# 11_Fan.net
KiCad netlist of a schematic drawn in Altium Designer
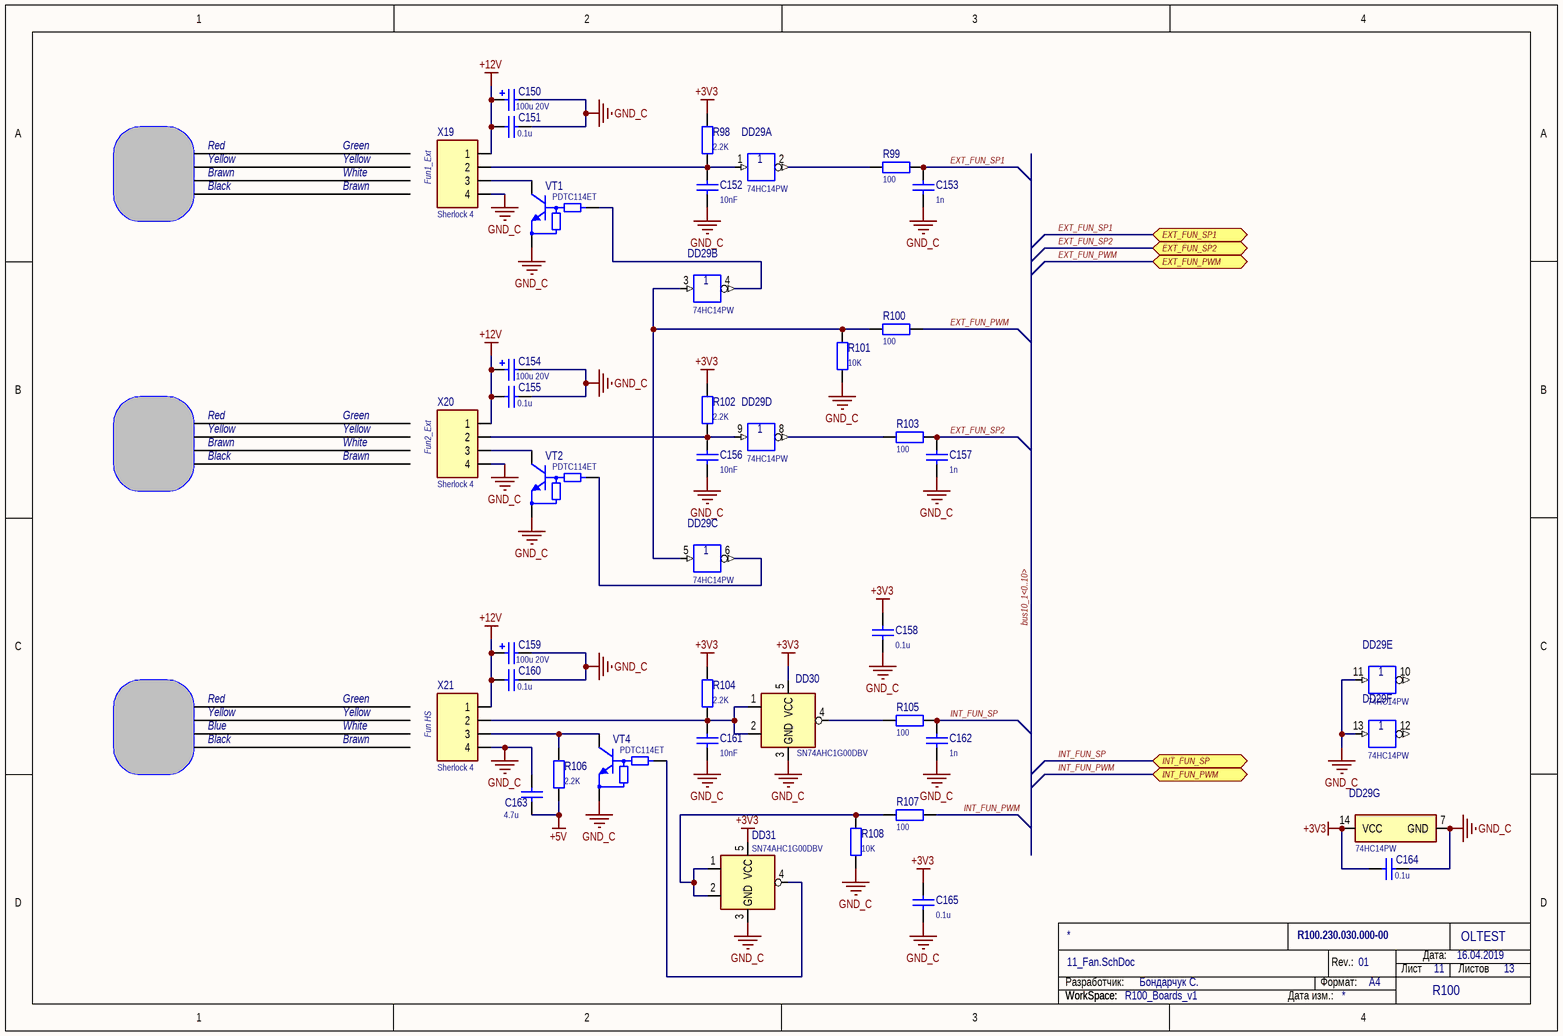
[diagram p0: 11_Fan.SchDoc]

(export (version "E")
  (design (tool "Eeschema 10.0.6"))
  (components
    (comp (ref "C150")
      (value "100u 20V")
      (footprint "mainLib:TAJD")
      (description "SMD SIZE D TANTALUM AVX 20V 10%")
      (fields (field (name "PARTNUMBER") "TAJD107K020RNJ") (field (name "MANUFACTURER") "AVX"))
      (libsource (lib "mainRCLib") (part "TECAP 100u 20V 10%"))
    )
    (comp (ref "C151")
      (value "0.1u")
      (footprint "mainLib:SMD_C_0603")
      (description "SMD C 0603 MURATA 50V 10% X7R")
      (fields (field (name "PARTNUMBER") "GRM188R71H104K") (field (name "MANUFACTURER") "MURATA"))
      (libsource (lib "mainRCLib") (part "C0603 0.1u 50V 10%"))
    )
    (comp (ref "C152")
      (value "10nF")
      (footprint "mainLib:SMD_C_0603")
      (description "SMD C 0603 MURATA 100V 10% X7R")
      (fields (field (name "PARTNUMBER") "GRJ188R72A103KE11#") (field (name "MANUFACTURER") "MURATA"))
      (libsource (lib "mainRCLib") (part "C0603 10nF 100V 10%"))
    )
    (comp (ref "C153")
      (value "1n")
      (footprint "mainLib:SMD_C_0603")
      (description "SMD C 0603 MURATA 50V 5% NP0")
      (fields (field (name "PARTNUMBER") "GRM1885C1H102JA01") (field (name "MANUFACTURER") "MURATA"))
      (libsource (lib "mainRCLib") (part "C0603 1n 50V 5%"))
    )
    (comp (ref "C154")
      (value "100u 20V")
      (footprint "mainLib:TAJD")
      (description "SMD SIZE D TANTALUM AVX 20V 10%")
      (fields (field (name "PARTNUMBER") "TAJD107K020RNJ") (field (name "MANUFACTURER") "AVX"))
      (libsource (lib "mainRCLib") (part "TECAP 100u 20V 10%"))
    )
    (comp (ref "C155")
      (value "0.1u")
      (footprint "mainLib:SMD_C_0603")
      (description "SMD C 0603 MURATA 50V 10% X7R")
      (fields (field (name "PARTNUMBER") "GRM188R71H104K") (field (name "MANUFACTURER") "MURATA"))
      (libsource (lib "mainRCLib") (part "C0603 0.1u 50V 10%"))
    )
    (comp (ref "C156")
      (value "10nF")
      (footprint "mainLib:SMD_C_0603")
      (description "SMD C 0603 MURATA 100V 10% X7R")
      (fields (field (name "PARTNUMBER") "GRJ188R72A103KE11#") (field (name "MANUFACTURER") "MURATA"))
      (libsource (lib "mainRCLib") (part "C0603 10nF 100V 10%"))
    )
    (comp (ref "C157")
      (value "1n")
      (footprint "mainLib:SMD_C_0603")
      (description "SMD C 0603 MURATA 50V 5% NP0")
      (fields (field (name "PARTNUMBER") "GRM1885C1H102JA01") (field (name "MANUFACTURER") "MURATA"))
      (libsource (lib "mainRCLib") (part "C0603 1n 50V 5%"))
    )
    (comp (ref "C158")
      (value "0.1u")
      (footprint "mainLib:SMD_C_0603")
      (description "SMD C 0603 MURATA 50V 10% X7R")
      (fields (field (name "PARTNUMBER") "GRM188R71H104K") (field (name "MANUFACTURER") "MURATA"))
      (libsource (lib "mainRCLib") (part "C0603 0.1u 50V 10%"))
    )
    (comp (ref "C159")
      (value "100u 20V")
      (footprint "mainLib:TAJD")
      (description "SMD SIZE D TANTALUM AVX 20V 10%")
      (fields (field (name "PARTNUMBER") "TAJD107K020RNJ") (field (name "MANUFACTURER") "AVX"))
      (libsource (lib "mainRCLib") (part "TECAP 100u 20V 10%"))
    )
    (comp (ref "C160")
      (value "0.1u")
      (footprint "mainLib:SMD_C_0603")
      (description "SMD C 0603 MURATA 50V 10% X7R")
      (fields (field (name "PARTNUMBER") "GRM188R71H104K") (field (name "MANUFACTURER") "MURATA"))
      (libsource (lib "mainRCLib") (part "C0603 0.1u 50V 10%"))
    )
    (comp (ref "C161")
      (value "10nF")
      (footprint "mainLib:SMD_C_0603")
      (description "SMD C 0603 MURATA 100V 10% X7R")
      (fields (field (name "PARTNUMBER") "GRJ188R72A103KE11#") (field (name "MANUFACTURER") "MURATA"))
      (libsource (lib "mainRCLib") (part "C0603 10nF 100V 10%"))
    )
    (comp (ref "C162")
      (value "1n")
      (footprint "mainLib:SMD_C_0603")
      (description "SMD C 0603 MURATA 50V 5% NP0")
      (fields (field (name "PARTNUMBER") "GRM1885C1H102JA01") (field (name "MANUFACTURER") "MURATA"))
      (libsource (lib "mainRCLib") (part "C0603 1n 50V 5%"))
    )
    (comp (ref "C163")
      (value "4.7u")
      (footprint "mainLib:SMD_C_0805")
      (description "SMD C 0805 MURATA 50V 5% NP0")
      (fields (field (name "PARTNUMBER") "GRM21BR61E475M") (field (name "MANUFACTURER") "MURATA"))
      (libsource (lib "mainRCLib") (part "C0805 4.7u 25V 20%  X5R"))
    )
    (comp (ref "C164")
      (value "0.1u")
      (footprint "mainLib:SMD_C_0603")
      (description "SMD C 0603 MURATA 50V 10% X7R")
      (fields (field (name "PARTNUMBER") "GRM188R71H104K") (field (name "MANUFACTURER") "MURATA"))
      (libsource (lib "mainRCLib") (part "C0603 0.1u 50V 10%"))
    )
    (comp (ref "C165")
      (value "0.1u")
      (footprint "mainLib:SMD_C_0603")
      (description "SMD C 0603 MURATA 50V 10% X7R")
      (fields (field (name "PARTNUMBER") "GRM188R71H104K") (field (name "MANUFACTURER") "MURATA"))
      (libsource (lib "mainRCLib") (part "C0603 0.1u 50V 10%"))
    )
    (comp (ref "DD29")
      (value "74HC14PW")
      (footprint "mainLib:TSSOP14")
      (description "Quadruple 2-Input Positive-OR Gates, PW0014A")
      (fields (field (name "MANUFACTURER") "Texas Instruments"))
      (libsource (lib "mainLib") (part "74HC14"))
    )
    (comp (ref "DD30")
      (value "SN74AHC1G00DBV")
      (footprint "mainLib:SOT-23(DBV)")
      (description "2-in NAND")
      (fields (field (name "MANUFACTURER") "Texas Instruments"))
      (libsource (lib "mainLib") (part "SN74AHC1G00DBV"))
    )
    (comp (ref "DD31")
      (value "SN74AHC1G00DBV")
      (footprint "mainLib:SOT-23(DBV)")
      (description "2-in NAND")
      (fields (field (name "MANUFACTURER") "Texas Instruments"))
      (libsource (lib "mainLib") (part "SN74AHC1G00DBV"))
    )
    (comp (ref "R98")
      (value "2.2K")
      (footprint "mainLib:SMD_R_0603")
      (description "SMD R 0603 VISHAY 0.1W 75V 1% 100ppm")
      (fields (field (name "PARTNUMBER") "CRCW06032K20FK") (field (name "MANUFACTURER") "VISHAY"))
      (libsource (lib "mainRCLib") (part "R0603 2.2K 1%"))
    )
    (comp (ref "R99")
      (value "100")
      (footprint "SMD_R_0603")
      (description "SMD R 0603 VISHAY 0.1W 75V 1% 100ppm")
      (fields (field (name "PARTNUMBER") "CRCW0603100RFK") (field (name "MANUFACTURER") "VISHAY"))
      (libsource (lib "mainRCLib") (part "R0603 100 1%"))
    )
    (comp (ref "R100")
      (value "100")
      (footprint "SMD_R_0603")
      (description "SMD R 0603 VISHAY 0.1W 75V 1% 100ppm")
      (fields (field (name "PARTNUMBER") "CRCW0603100RFK") (field (name "MANUFACTURER") "VISHAY"))
      (libsource (lib "mainRCLib") (part "R0603 100 1%"))
    )
    (comp (ref "R101")
      (value "10K")
      (footprint "SMD_R_0603")
      (description "SMD R 0603 VISHAY 0.1W 75V 1% 100ppm")
      (fields (field (name "PARTNUMBER") "CRCW060310K0FK") (field (name "MANUFACTURER") "VISHAY"))
      (libsource (lib "mainRCLib") (part "R0603 10К 1%"))
    )
    (comp (ref "R102")
      (value "2.2K")
      (footprint "mainLib:SMD_R_0603")
      (description "SMD R 0603 VISHAY 0.1W 75V 1% 100ppm")
      (fields (field (name "PARTNUMBER") "CRCW06032K20FK") (field (name "MANUFACTURER") "VISHAY"))
      (libsource (lib "mainRCLib") (part "R0603 2.2K 1%"))
    )
    (comp (ref "R103")
      (value "100")
      (footprint "SMD_R_0603")
      (description "SMD R 0603 VISHAY 0.1W 75V 1% 100ppm")
      (fields (field (name "PARTNUMBER") "CRCW0603100RFK") (field (name "MANUFACTURER") "VISHAY"))
      (libsource (lib "mainRCLib") (part "R0603 100 1%"))
    )
    (comp (ref "R104")
      (value "2.2K")
      (footprint "mainLib:SMD_R_0603")
      (description "SMD R 0603 VISHAY 0.1W 75V 1% 100ppm")
      (fields (field (name "PARTNUMBER") "CRCW06032K20FK") (field (name "MANUFACTURER") "VISHAY"))
      (libsource (lib "mainRCLib") (part "R0603 2.2K 1%"))
    )
    (comp (ref "R105")
      (value "100")
      (footprint "SMD_R_0603")
      (description "SMD R 0603 VISHAY 0.1W 75V 1% 100ppm")
      (fields (field (name "PARTNUMBER") "CRCW0603100RFK") (field (name "MANUFACTURER") "VISHAY"))
      (libsource (lib "mainRCLib") (part "R0603 100 1%"))
    )
    (comp (ref "R106")
      (value "2.2K")
      (footprint "mainLib:SMD_R_0603")
      (description "SMD R 0603 VISHAY 0.1W 75V 1% 100ppm")
      (fields (field (name "PARTNUMBER") "CRCW06032K20FK") (field (name "MANUFACTURER") "VISHAY"))
      (libsource (lib "mainRCLib") (part "R0603 2.2K 1%"))
    )
    (comp (ref "R107")
      (value "100")
      (footprint "SMD_R_0603")
      (description "SMD R 0603 VISHAY 0.1W 75V 1% 100ppm")
      (fields (field (name "PARTNUMBER") "CRCW0603100RFK") (field (name "MANUFACTURER") "VISHAY"))
      (libsource (lib "mainRCLib") (part "R0603 100 1%"))
    )
    (comp (ref "R108")
      (value "10K")
      (footprint "SMD_R_0603")
      (description "SMD R 0603 VISHAY 0.1W 75V 1% 100ppm")
      (fields (field (name "PARTNUMBER") "CRCW060310K0FK") (field (name "MANUFACTURER") "VISHAY"))
      (libsource (lib "mainRCLib") (part "R0603 10К 1%"))
    )
    (comp (ref "VT1")
      (value "PDTC114ET")
      (footprint "mainLib:SOT23-3")
      (description "Digital Transistor (BRT), R1=10 kOhm, R2=10 kOhm, NPN Transistor")
      (fields (field (name "MANUFACTURER") "On Semiconductor"))
      (libsource (lib "mainLib") (part "PDTC114ET"))
    )
    (comp (ref "VT2")
      (value "PDTC114ET")
      (footprint "mainLib:SOT23-3")
      (description "Digital Transistor (BRT), R1=10 kOhm, R2=10 kOhm, NPN Transistor")
      (fields (field (name "MANUFACTURER") "On Semiconductor"))
      (libsource (lib "mainLib") (part "PDTC114ET"))
    )
    (comp (ref "VT4")
      (value "PDTC114ET")
      (footprint "mainLib:SOT23-3")
      (description "Digital Transistor (BRT), R1=10 kOhm, R2=10 kOhm, NPN Transistor")
      (fields (field (name "MANUFACTURER") "On Semiconductor"))
      (libsource (lib "mainLib") (part "PDTC114ET"))
    )
    (comp (ref "X19")
      (value "Sherlock 4")
      (footprint "35362-0450")
      (description "Sherlock 4 Top, 2A 125V 2mm")
      (fields (field (name "PARTNUMBER") "35362-0450") (field (name "MANUFACTURER") "MOLEX"))
      (libsource (lib "mainLib") (part "35362-0450"))
    )
    (comp (ref "X20")
      (value "Sherlock 4")
      (footprint "35362-0450")
      (description "Sherlock 4 Top, 2A 125V 2mm")
      (fields (field (name "PARTNUMBER") "35362-0450") (field (name "MANUFACTURER") "MOLEX"))
      (libsource (lib "mainLib") (part "35362-0450"))
    )
    (comp (ref "X21")
      (value "Sherlock 4")
      (footprint "35362-0450")
      (description "Sherlock 4 Top, 2A 125V 2mm")
      (fields (field (name "PARTNUMBER") "35362-0450") (field (name "MANUFACTURER") "MOLEX"))
      (libsource (lib "mainLib") (part "35362-0450"))
    )
  )
  (nets
    (net (code "2") (name "+3V3") (class "Default")
      (node (ref "C158") (pin "2") (pinfunction "2_2") (pintype "passive"))
      (node (ref "C164") (pin "1") (pinfunction "1_1") (pintype "passive"))
      (node (ref "C165") (pin "2") (pinfunction "2_2") (pintype "passive"))
      (node (ref "DD29") (pin "14") (pinfunction "VCC_14") (pintype "power_in"))
      (node (ref "DD30") (pin "5") (pinfunction "VCC_5") (pintype "passive"))
      (node (ref "DD31") (pin "5") (pinfunction "VCC_5") (pintype "passive"))
      (node (ref "R102") (pin "2") (pinfunction "2_2") (pintype "passive"))
      (node (ref "R104") (pin "2") (pinfunction "2_2") (pintype "passive"))
      (node (ref "R98") (pin "2") (pinfunction "2_2") (pintype "passive"))
    )
    (net (code "3") (name "+5V") (class "Default")
      (node (ref "C163") (pin "1") (pinfunction "1_1") (pintype "passive"))
      (node (ref "R106") (pin "1") (pinfunction "1_1") (pintype "passive"))
    )
    (net (code "4") (name "+12V") (class "Default")
      (node (ref "C150") (pin "1") (pinfunction "1_1") (pintype "passive"))
      (node (ref "C151") (pin "1") (pinfunction "1_1") (pintype "passive"))
      (node (ref "C154") (pin "1") (pinfunction "1_1") (pintype "passive"))
      (node (ref "C155") (pin "1") (pinfunction "1_1") (pintype "passive"))
      (node (ref "C159") (pin "1") (pinfunction "1_1") (pintype "passive"))
      (node (ref "C160") (pin "1") (pinfunction "1_1") (pintype "passive"))
      (node (ref "X19") (pin "1") (pinfunction "1_1") (pintype "passive"))
      (node (ref "X20") (pin "1") (pinfunction "1_1") (pintype "passive"))
      (node (ref "X21") (pin "1") (pinfunction "1_1") (pintype "passive"))
    )
    (net (code "5") (name "/EXT_FUN_PWM") (class "Default")
      (node (ref "R100") (pin "2") (pinfunction "2_2") (pintype "passive"))
    )
    (net (code "6") (name "/EXT_FUN_SP1") (class "Default")
      (node (ref "C153") (pin "2") (pinfunction "2_2") (pintype "passive"))
      (node (ref "R99") (pin "2") (pinfunction "2_2") (pintype "passive"))
    )
    (net (code "7") (name "/EXT_FUN_SP2") (class "Default")
      (node (ref "C157") (pin "2") (pinfunction "2_2") (pintype "passive"))
      (node (ref "R103") (pin "2") (pinfunction "2_2") (pintype "passive"))
    )
    (net (code "8") (name "/INT_FUN_PWM") (class "Default")
      (node (ref "R107") (pin "2") (pinfunction "2_2") (pintype "passive"))
    )
    (net (code "9") (name "/INT_FUN_SP") (class "Default")
      (node (ref "C162") (pin "2") (pinfunction "2_2") (pintype "passive"))
      (node (ref "R105") (pin "2") (pinfunction "2_2") (pintype "passive"))
    )
    (net (code "11") (name "GND_C") (class "Default")
      (node (ref "C150") (pin "2") (pinfunction "2_2") (pintype "passive"))
      (node (ref "C151") (pin "2") (pinfunction "2_2") (pintype "passive"))
      (node (ref "C152") (pin "2") (pinfunction "2_2") (pintype "passive"))
      (node (ref "C153") (pin "1") (pinfunction "1_1") (pintype "passive"))
      (node (ref "C154") (pin "2") (pinfunction "2_2") (pintype "passive"))
      (node (ref "C155") (pin "2") (pinfunction "2_2") (pintype "passive"))
      (node (ref "C156") (pin "2") (pinfunction "2_2") (pintype "passive"))
      (node (ref "C157") (pin "1") (pinfunction "1_1") (pintype "passive"))
      (node (ref "C158") (pin "1") (pinfunction "1_1") (pintype "passive"))
      (node (ref "C159") (pin "2") (pinfunction "2_2") (pintype "passive"))
      (node (ref "C160") (pin "2") (pinfunction "2_2") (pintype "passive"))
      (node (ref "C161") (pin "2") (pinfunction "2_2") (pintype "passive"))
      (node (ref "C162") (pin "1") (pinfunction "1_1") (pintype "passive"))
      (node (ref "C163") (pin "2") (pinfunction "2_2") (pintype "passive"))
      (node (ref "C164") (pin "2") (pinfunction "2_2") (pintype "passive"))
      (node (ref "C165") (pin "1") (pinfunction "1_1") (pintype "passive"))
      (node (ref "DD29") (pin "11") (pinfunction "5A_11") (pintype "input"))
      (node (ref "DD29") (pin "13") (pinfunction "6A_13") (pintype "input"))
      (node (ref "DD29") (pin "7") (pinfunction "GND_7") (pintype "power_in"))
      (node (ref "DD30") (pin "3") (pinfunction "GND_3") (pintype "passive"))
      (node (ref "DD31") (pin "3") (pinfunction "GND_3") (pintype "passive"))
      (node (ref "R101") (pin "1") (pinfunction "1_1") (pintype "passive"))
      (node (ref "R108") (pin "1") (pinfunction "1_1") (pintype "passive"))
      (node (ref "VT1") (pin "2") (pinfunction "E_2") (pintype "passive"))
      (node (ref "VT2") (pin "2") (pinfunction "E_2") (pintype "passive"))
      (node (ref "VT4") (pin "2") (pinfunction "E_2") (pintype "passive"))
      (node (ref "X19") (pin "4") (pinfunction "4_4") (pintype "passive"))
      (node (ref "X20") (pin "4") (pinfunction "4_4") (pintype "passive"))
      (node (ref "X21") (pin "4") (pinfunction "4_4") (pintype "passive"))
    )
    (net (code "12") (name "Net-(C161-Pad1)") (class "Default")
      (node (ref "C161") (pin "1") (pinfunction "1_1") (pintype "passive"))
      (node (ref "DD30") (pin "1") (pintype "passive"))
      (node (ref "DD30") (pin "2") (pintype "passive"))
      (node (ref "R104") (pin "1") (pinfunction "1_1") (pintype "passive"))
      (node (ref "X21") (pin "2") (pinfunction "2_2") (pintype "passive"))
    )
    (net (code "13") (name "Net-(DD29A-1A)") (class "Default")
      (node (ref "C152") (pin "1") (pinfunction "1_1") (pintype "passive"))
      (node (ref "DD29") (pin "1") (pinfunction "1A_1") (pintype "input"))
      (node (ref "R98") (pin "1") (pinfunction "1_1") (pintype "passive"))
      (node (ref "X19") (pin "2") (pinfunction "2_2") (pintype "passive"))
    )
    (net (code "14") (name "Net-(DD29A-1Y)") (class "Default")
      (node (ref "DD29") (pin "2") (pinfunction "1Y_2") (pintype "output"))
      (node (ref "R99") (pin "1") (pinfunction "1_1") (pintype "passive"))
    )
    (net (code "15") (name "Net-(DD29B-2A)") (class "Default")
      (node (ref "DD29") (pin "3") (pinfunction "2A_3") (pintype "input"))
      (node (ref "DD29") (pin "5") (pinfunction "3A_5") (pintype "input"))
      (node (ref "R100") (pin "1") (pinfunction "1_1") (pintype "passive"))
      (node (ref "R101") (pin "2") (pinfunction "2_2") (pintype "passive"))
    )
    (net (code "16") (name "Net-(DD29B-2Y)") (class "Default")
      (node (ref "DD29") (pin "4") (pinfunction "2Y_4") (pintype "output"))
      (node (ref "VT1") (pin "1") (pinfunction "B_1") (pintype "passive"))
    )
    (net (code "17") (name "Net-(DD29C-3Y)") (class "Default")
      (node (ref "DD29") (pin "6") (pinfunction "3Y_6") (pintype "output"))
      (node (ref "VT2") (pin "1") (pinfunction "B_1") (pintype "passive"))
    )
    (net (code "18") (name "Net-(DD29D-4A)") (class "Default")
      (node (ref "C156") (pin "1") (pinfunction "1_1") (pintype "passive"))
      (node (ref "DD29") (pin "9") (pinfunction "4A_9") (pintype "input"))
      (node (ref "R102") (pin "1") (pinfunction "1_1") (pintype "passive"))
      (node (ref "X20") (pin "2") (pinfunction "2_2") (pintype "passive"))
    )
    (net (code "19") (name "Net-(DD29D-4Y)") (class "Default")
      (node (ref "DD29") (pin "8") (pinfunction "4Y_8") (pintype "output"))
      (node (ref "R103") (pin "1") (pinfunction "1_1") (pintype "passive"))
    )
    (net (code "20") (name "Net-(DD30-Pad4)") (class "Default")
      (node (ref "DD30") (pin "4") (pintype "passive"))
      (node (ref "R105") (pin "1") (pinfunction "1_1") (pintype "passive"))
    )
    (net (code "21") (name "Net-(DD31-Pad1)") (class "Default")
      (node (ref "DD31") (pin "1") (pintype "passive"))
      (node (ref "DD31") (pin "2") (pintype "passive"))
      (node (ref "R107") (pin "1") (pinfunction "1_1") (pintype "passive"))
      (node (ref "R108") (pin "2") (pinfunction "2_2") (pintype "passive"))
    )
    (net (code "22") (name "Net-(VT1-C)") (class "Default")
      (node (ref "VT1") (pin "3") (pinfunction "C_3") (pintype "passive"))
      (node (ref "X19") (pin "3") (pinfunction "3_3") (pintype "passive"))
    )
    (net (code "23") (name "Net-(VT2-C)") (class "Default")
      (node (ref "VT2") (pin "3") (pinfunction "C_3") (pintype "passive"))
      (node (ref "X20") (pin "3") (pinfunction "3_3") (pintype "passive"))
    )
    (net (code "24") (name "Net-(VT4-B)") (class "Default")
      (node (ref "DD31") (pin "4") (pintype "passive"))
      (node (ref "VT4") (pin "1") (pinfunction "B_1") (pintype "passive"))
    )
    (net (code "25") (name "Net-(VT4-C)") (class "Default")
      (node (ref "R106") (pin "2") (pinfunction "2_2") (pintype "passive"))
      (node (ref "VT4") (pin "3") (pinfunction "C_3") (pintype "passive"))
      (node (ref "X21") (pin "3") (pinfunction "3_3") (pintype "passive"))
    )
    (net (code "26") (name "unconnected-(DD29E-5Y-Pad10)") (class "Default")
      (node (ref "DD29") (pin "10") (pinfunction "5Y_10") (pintype "output"))
    )
    (net (code "27") (name "unconnected-(DD29F-6Y-Pad12)") (class "Default")
      (node (ref "DD29") (pin "12") (pinfunction "6Y_12") (pintype "output"))
    )
  )
)
